# delta-pcb-main.net
KiCad netlist of a schematic drawn in Altium Designer
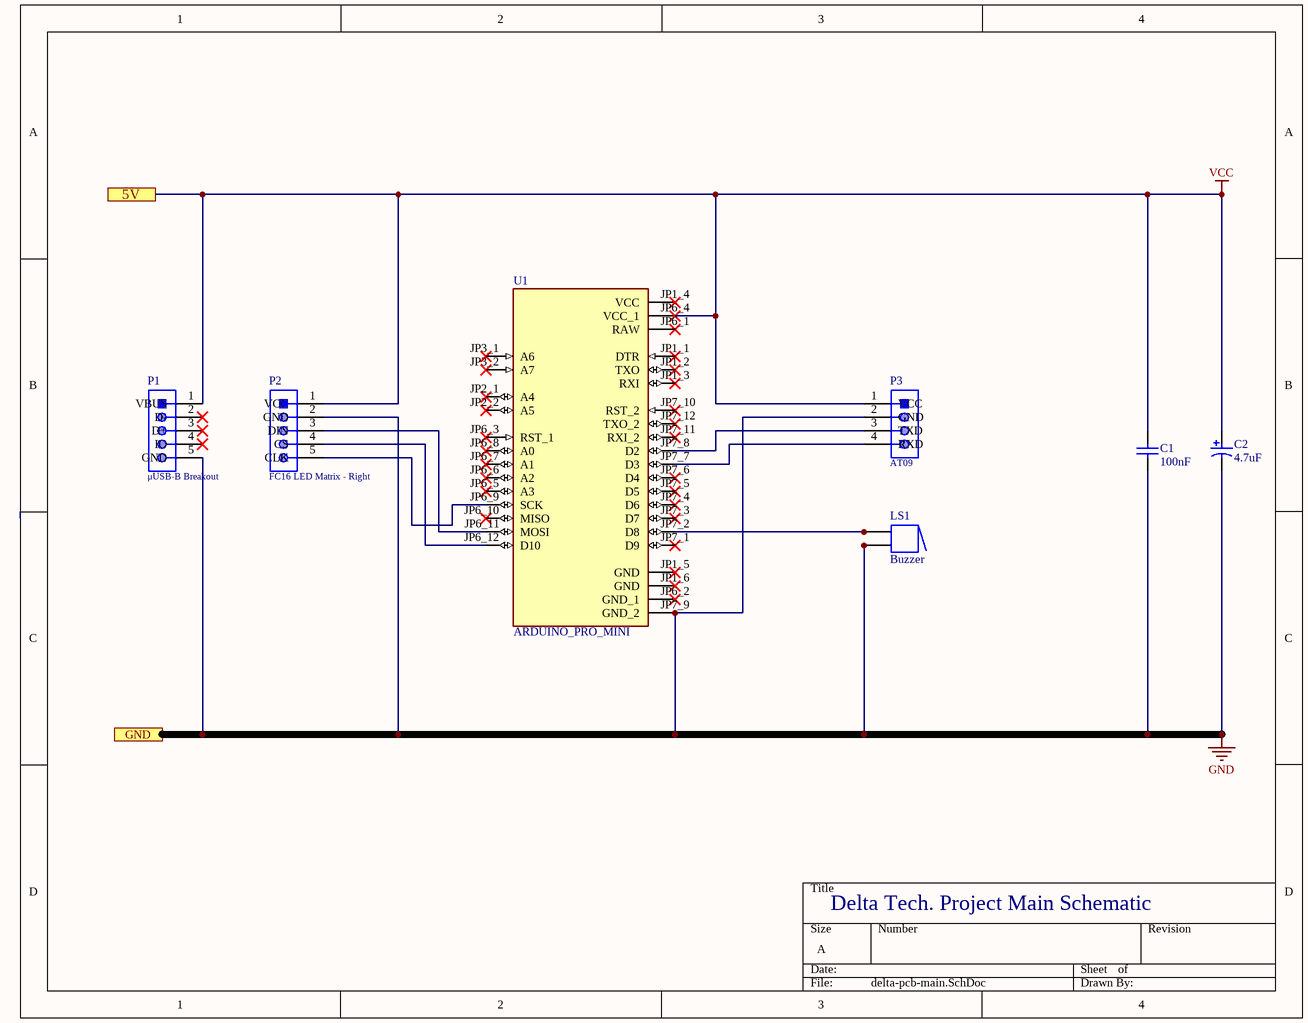
[diagram p0: delta-pcb-main.SchDoc]

(export (version "E")
  (design (tool "Eeschema 10.0.6"))
  (components
    (comp (ref "C1")
      (value "100nF")
      (footprint "VISH-K104K15X7RF5TL2")
      (description "Ceramic Capacitor, 100 nF, +/- 10%, 50 V, -55 to 125 degC, 2-Pin THD, RoHS, Tape and Reel")
      (fields (field (name "MANUFACTURER") "Vishay") (field (name "TOLERANCE") "±10%"))
      (libsource (lib "Altium Content Vault") (part "CAP-NP-2"))
    )
    (comp (ref "C2")
      (value "4.7uF")
      (footprint "CAPPR55-200-1100X500X1200")
      (description "Aluminum Electrolytic Capacitor, 4.7 uF, +/- 20%, 50 V, -40 to 85 degC, 2-Pin THD, RoHS, Bulk")
      (fields (field (name "VOLTAGE") "50V") (field (name "MANUFACTURER") "Panasonic"))
      (libsource (lib "Altium Content Vault") (part "CAP-P-2"))
    )
    (comp (ref "LS1")
      (value "Buzzer")
      (footprint "ABSM-1574")
      (description "Magnetic Transducer Buzzer")
      (fields (field (name "PUBLISHER") "Altium Limited"))
      (libsource (lib "Miscellaneous Devices") (part "Buzzer"))
    )
    (comp (ref "P1")
      (value "μUSB-B Breakout")
      (footprint "61300511121")
      (description "THT Vertical Pin Header WR-PHD, Pitch 2.54 mm, Single Row, 5 pins")
      (fields
        (field (name "PART NUMBER") "61300511121")
        (field (name "MANUFACTURER") "Wurth Elektronik")
        (field (name "PUBLISHER") "WurthElektronik")
      )
      (libsource (lib "Altium Content Vault") (part "WE-CN-1P-M-R5"))
    )
    (comp (ref "P2")
      (value "FC16 LED Matrix - Right")
      (footprint "61300511121")
      (description "THT Vertical Pin Header WR-PHD, Pitch 2.54 mm, Single Row, 5 pins")
      (fields
        (field (name "PART NUMBER") "61300511121")
        (field (name "MANUFACTURER") "Wurth Elektronik")
        (field (name "PUBLISHER") "WurthElektronik")
      )
      (libsource (lib "Altium Content Vault") (part "WE-CN-1P-M-R5"))
    )
    (comp (ref "P3")
      (value "AT09")
      (footprint "61300411121")
      (description "THT Vertical Pin Header WR-PHD, Pitch 2.54 mm, Single Row, 4 pins")
      (fields
        (field (name "MANUFACTURER") "Wurth Elektronik")
        (field (name "PART NUMBER") "61300411121")
        (field (name "PUBLISHER") "WurthElektronik")
      )
      (libsource (lib "Altium Content Vault") (part "WE-CN-1P-M-R4"))
    )
    (comp (ref "U1")
      (value "ARDUINO_PRO_MINI")
      (footprint "MODULE_ARDUINO_PRO_MINI")
      (description "ATmega328 Arduino Pro Mini 328 5V/16MHz AVRÂ® ATmega AVR MCU 8-Bit Embedded Evaluation Board")
      (fields (field (name "MF") "{'manufacturer': u'Arduino'}"))
      (libsource (lib "SnapEDA_Library") (part "ARDUINO_PRO_MINI"))
    )
  )
  (nets
    (net (code "1") (name "GND") (class "Default")
      (node (ref "C1") (pin "1") (pinfunction "1_1") (pintype "passive"))
      (node (ref "C2") (pin "2") (pinfunction "2_2") (pintype "passive"))
      (node (ref "LS1") (pin "2") (pinfunction "2_2") (pintype "passive"))
      (node (ref "LS1") (pin "2A") (pinfunction "2A_2A") (pintype "passive"))
      (node (ref "P1") (pin "5") (pinfunction "GND_5") (pintype "passive"))
      (node (ref "P2") (pin "2") (pinfunction "D-_2") (pintype "passive"))
      (node (ref "P3") (pin "2") (pinfunction "GND_2") (pintype "passive"))
      (node (ref "U1") (pin "JP7_9") (pinfunction "GND_2_JP7_9") (pintype "power_in"))
    )
    (net (code "2") (name "Net-(P2-D+)") (class "Default")
      (node (ref "P2") (pin "3") (pinfunction "D+_3") (pintype "passive"))
      (node (ref "U1") (pin "JP6_11") (pinfunction "MOSI_JP6_11") (pintype "bidirectional"))
    )
    (net (code "3") (name "Net-(P2-GND)") (class "Default")
      (node (ref "P2") (pin "5") (pinfunction "GND_5") (pintype "passive"))
      (node (ref "U1") (pin "JP6_9") (pinfunction "SCK_JP6_9") (pintype "bidirectional"))
    )
    (net (code "4") (name "Net-(P2-IO)") (class "Default")
      (node (ref "P2") (pin "4") (pinfunction "IO_4") (pintype "passive"))
      (node (ref "U1") (pin "JP6_12") (pinfunction "D10_JP6_12") (pintype "bidirectional"))
    )
    (net (code "5") (name "Net-(P3-RXD)") (class "Default")
      (node (ref "P3") (pin "4") (pinfunction "RXD_4") (pintype "passive"))
      (node (ref "U1") (pin "JP7_7") (pinfunction "D3_JP7_7") (pintype "bidirectional"))
    )
    (net (code "6") (name "Net-(P3-TXD)") (class "Default")
      (node (ref "P3") (pin "3") (pinfunction "TXD_3") (pintype "passive"))
      (node (ref "U1") (pin "JP7_8") (pinfunction "D2_JP7_8") (pintype "bidirectional"))
    )
    (net (code "7") (name "Net-(U1-D8)") (class "Default")
      (node (ref "LS1") (pin "1") (pinfunction "1_1") (pintype "passive"))
      (node (ref "LS1") (pin "1A") (pinfunction "1A_1A") (pintype "passive"))
      (node (ref "U1") (pin "JP7_2") (pinfunction "D8_JP7_2") (pintype "bidirectional"))
    )
    (net (code "8") (name "VCC") (class "Default")
      (node (ref "C1") (pin "2") (pinfunction "2_2") (pintype "passive"))
      (node (ref "C2") (pin "1") (pinfunction "1_1") (pintype "passive"))
      (node (ref "P1") (pin "1") (pinfunction "VBUS_1") (pintype "passive"))
      (node (ref "P2") (pin "1") (pinfunction "VBUS_1") (pintype "passive"))
      (node (ref "P3") (pin "1") (pinfunction "VCC_1") (pintype "passive"))
      (node (ref "U1") (pin "JP6_4") (pinfunction "VCC_1_JP6_4") (pintype "power_in"))
    )
    (net (code "9") (name "unconnected-(P1-D+-Pad3)") (class "Default")
      (node (ref "P1") (pin "3") (pinfunction "D+_3") (pintype "passive+no_connect"))
    )
    (net (code "10") (name "unconnected-(P1-D--Pad2)") (class "Default")
      (node (ref "P1") (pin "2") (pinfunction "D-_2") (pintype "passive+no_connect"))
    )
    (net (code "11") (name "unconnected-(P1-IO-Pad4)") (class "Default")
      (node (ref "P1") (pin "4") (pinfunction "IO_4") (pintype "passive+no_connect"))
    )
    (net (code "12") (name "unconnected-(U1-A0-PadJP6_8)") (class "Default")
      (node (ref "U1") (pin "JP6_8") (pinfunction "A0_JP6_8") (pintype "bidirectional+no_connect"))
    )
    (net (code "13") (name "unconnected-(U1-A1-PadJP6_7)") (class "Default")
      (node (ref "U1") (pin "JP6_7") (pinfunction "A1_JP6_7") (pintype "bidirectional+no_connect"))
    )
    (net (code "14") (name "unconnected-(U1-A2-PadJP6_6)") (class "Default")
      (node (ref "U1") (pin "JP6_6") (pinfunction "A2_JP6_6") (pintype "bidirectional+no_connect"))
    )
    (net (code "15") (name "unconnected-(U1-A3-PadJP6_5)") (class "Default")
      (node (ref "U1") (pin "JP6_5") (pinfunction "A3_JP6_5") (pintype "bidirectional+no_connect"))
    )
    (net (code "16") (name "unconnected-(U1-A4-PadJP2_1)") (class "Default")
      (node (ref "U1") (pin "JP2_1") (pinfunction "A4_JP2_1") (pintype "bidirectional+no_connect"))
    )
    (net (code "17") (name "unconnected-(U1-A5-PadJP2_2)") (class "Default")
      (node (ref "U1") (pin "JP2_2") (pinfunction "A5_JP2_2") (pintype "bidirectional+no_connect"))
    )
    (net (code "18") (name "unconnected-(U1-A6-PadJP3_1)") (class "Default")
      (node (ref "U1") (pin "JP3_1") (pinfunction "A6_JP3_1") (pintype "input+no_connect"))
    )
    (net (code "19") (name "unconnected-(U1-A7-PadJP3_2)") (class "Default")
      (node (ref "U1") (pin "JP3_2") (pinfunction "A7_JP3_2") (pintype "input+no_connect"))
    )
    (net (code "20") (name "unconnected-(U1-D4-PadJP7_6)") (class "Default")
      (node (ref "U1") (pin "JP7_6") (pinfunction "D4_JP7_6") (pintype "bidirectional+no_connect"))
    )
    (net (code "21") (name "unconnected-(U1-D5-PadJP7_5)") (class "Default")
      (node (ref "U1") (pin "JP7_5") (pinfunction "D5_JP7_5") (pintype "bidirectional+no_connect"))
    )
    (net (code "22") (name "unconnected-(U1-D6-PadJP7_4)") (class "Default")
      (node (ref "U1") (pin "JP7_4") (pinfunction "D6_JP7_4") (pintype "bidirectional+no_connect"))
    )
    (net (code "23") (name "unconnected-(U1-D7-PadJP7_3)") (class "Default")
      (node (ref "U1") (pin "JP7_3") (pinfunction "D7_JP7_3") (pintype "bidirectional+no_connect"))
    )
    (net (code "24") (name "unconnected-(U1-D9-PadJP7_1)") (class "Default")
      (node (ref "U1") (pin "JP7_1") (pinfunction "D9_JP7_1") (pintype "bidirectional+no_connect"))
    )
    (net (code "25") (name "unconnected-(U1-DTR-PadJP1_1)") (class "Default")
      (node (ref "U1") (pin "JP1_1") (pinfunction "DTR_JP1_1") (pintype "input+no_connect"))
    )
    (net (code "26") (name "unconnected-(U1-GND-PadJP1_5)") (class "Default")
      (node (ref "U1") (pin "JP1_5") (pinfunction "GND_JP1_5") (pintype "power_in+no_connect"))
    )
    (net (code "27") (name "unconnected-(U1-GND-PadJP1_6)") (class "Default")
      (node (ref "U1") (pin "JP1_6") (pinfunction "GND_JP1_6") (pintype "power_in+no_connect"))
    )
    (net (code "28") (name "unconnected-(U1-GND_1-PadJP6_2)") (class "Default")
      (node (ref "U1") (pin "JP6_2") (pinfunction "GND_1_JP6_2") (pintype "power_in+no_connect"))
    )
    (net (code "29") (name "unconnected-(U1-MISO-PadJP6_10)") (class "Default")
      (node (ref "U1") (pin "JP6_10") (pinfunction "MISO_JP6_10") (pintype "bidirectional+no_connect"))
    )
    (net (code "30") (name "unconnected-(U1-RAW-PadJP6_1)") (class "Default")
      (node (ref "U1") (pin "JP6_1") (pinfunction "RAW_JP6_1") (pintype "power_in+no_connect"))
    )
    (net (code "31") (name "unconnected-(U1-RST_1-PadJP6_3)") (class "Default")
      (node (ref "U1") (pin "JP6_3") (pinfunction "RST_1_JP6_3") (pintype "input+no_connect"))
    )
    (net (code "32") (name "unconnected-(U1-RST_2-PadJP7_10)") (class "Default")
      (node (ref "U1") (pin "JP7_10") (pinfunction "RST_2_JP7_10") (pintype "input+no_connect"))
    )
    (net (code "33") (name "unconnected-(U1-RXI-PadJP1_3)") (class "Default")
      (node (ref "U1") (pin "JP1_3") (pinfunction "RXI_JP1_3") (pintype "bidirectional+no_connect"))
    )
    (net (code "34") (name "unconnected-(U1-RXI_2-PadJP7_11)") (class "Default")
      (node (ref "U1") (pin "JP7_11") (pinfunction "RXI_2_JP7_11") (pintype "bidirectional+no_connect"))
    )
    (net (code "35") (name "unconnected-(U1-TXO-PadJP1_2)") (class "Default")
      (node (ref "U1") (pin "JP1_2") (pinfunction "TXO_JP1_2") (pintype "bidirectional+no_connect"))
    )
    (net (code "36") (name "unconnected-(U1-TXO_2-PadJP7_12)") (class "Default")
      (node (ref "U1") (pin "JP7_12") (pinfunction "TXO_2_JP7_12") (pintype "bidirectional+no_connect"))
    )
    (net (code "37") (name "unconnected-(U1-VCC-PadJP1_4)") (class "Default")
      (node (ref "U1") (pin "JP1_4") (pinfunction "VCC_JP1_4") (pintype "power_in+no_connect"))
    )
  )
)
